# schemat2.net
KiCad netlist of a schematic drawn in EAGLE
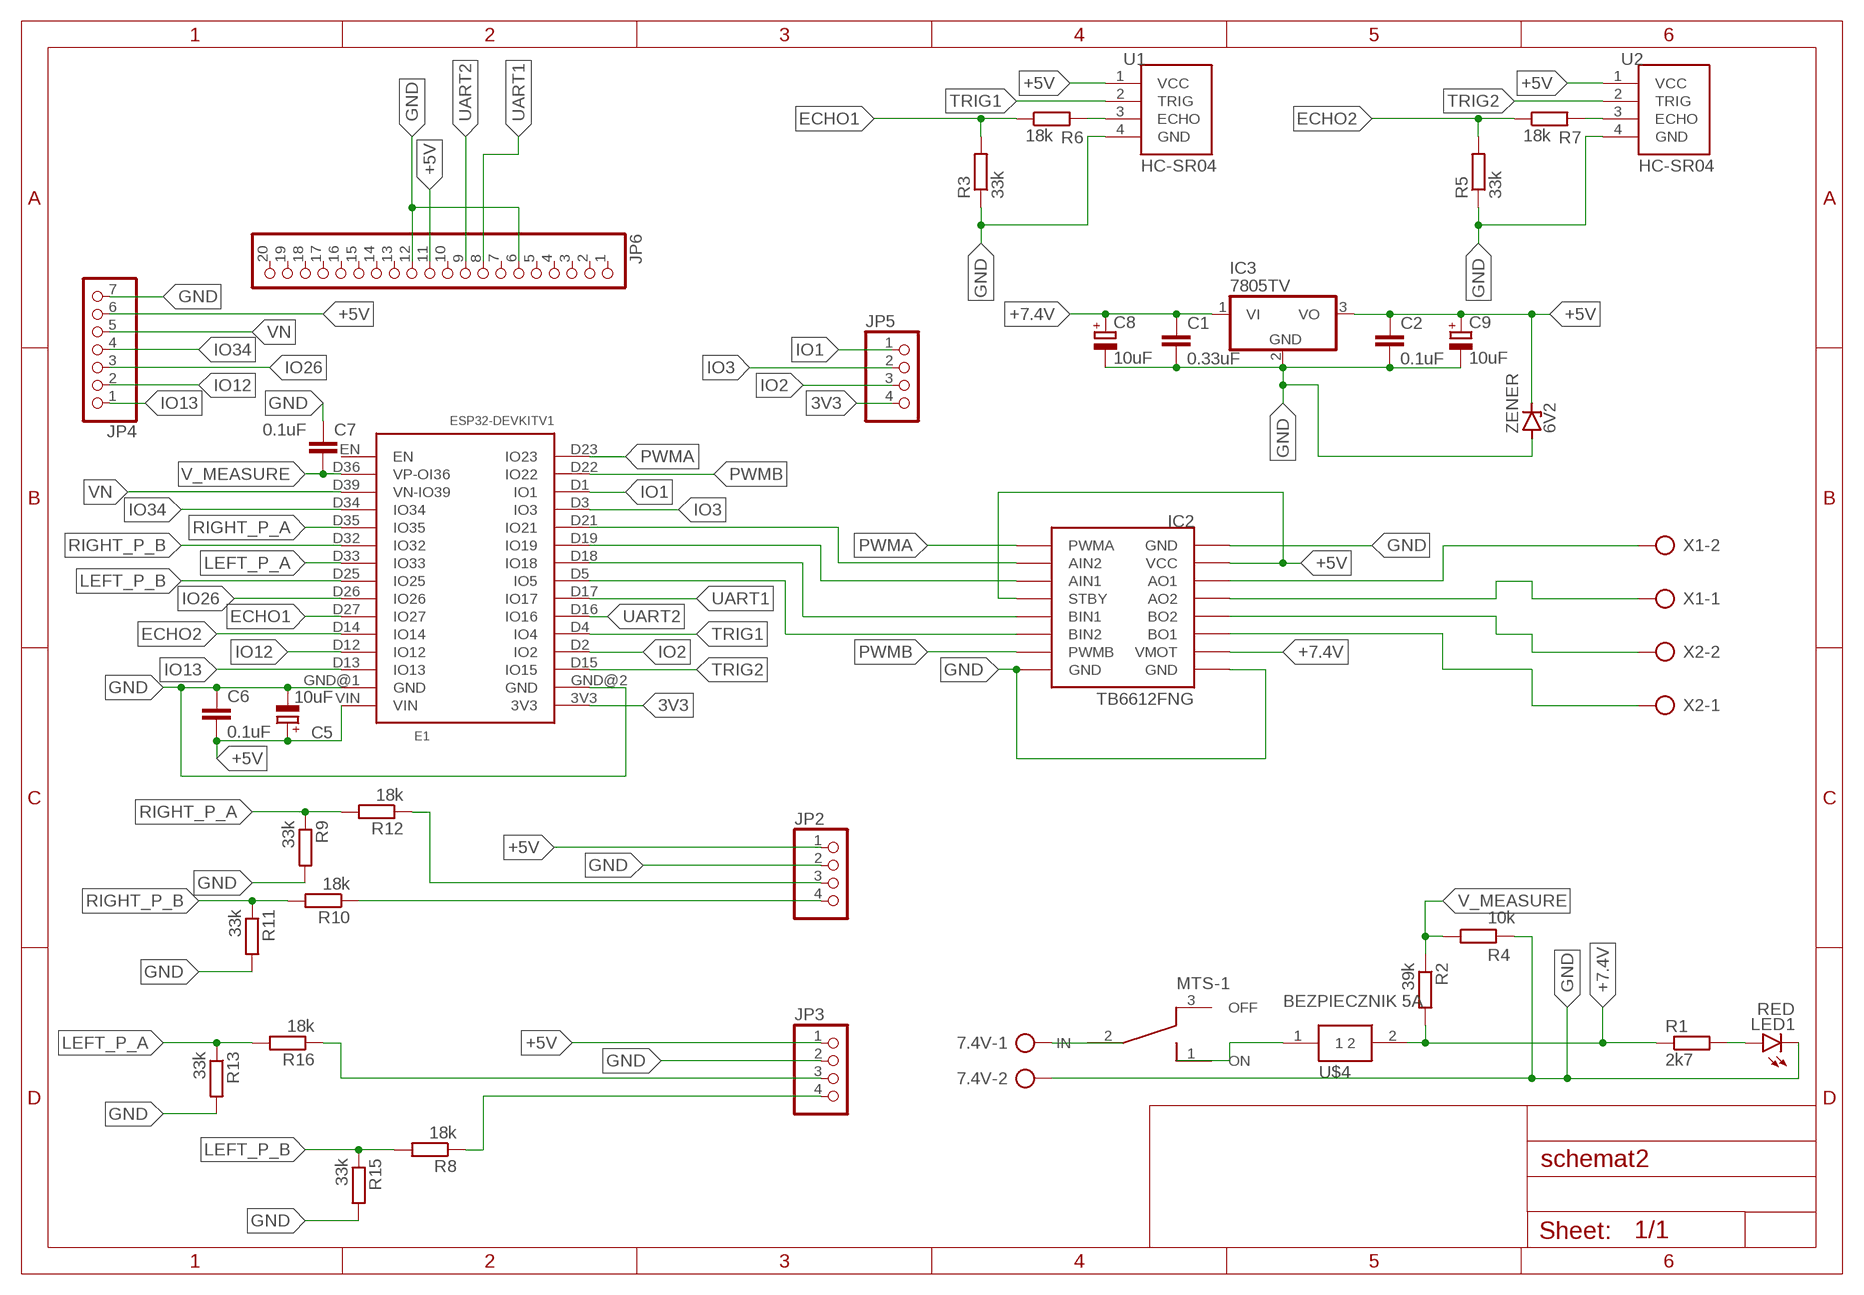
[diagram p0: schematic, sheet 1]

(export (version "E")
  (design (tool "Eeschema 10.0.6"))
  (components
    (comp (ref "7.4V")
      (value "AK500/2")
      (footprint "eagle-import:AK500_2")
      (libsource (lib "eagle-import") (part "AK500/2"))
    )
    (comp (ref "C1")
      (value "0.33uF")
      (footprint "eagle-import:C025-024X044")
      (libsource (lib "eagle-import") (part "C-EU025-024X044"))
    )
    (comp (ref "C2")
      (value "0.1uF")
      (footprint "eagle-import:C025-024X044")
      (libsource (lib "eagle-import") (part "C-EU025-024X044"))
    )
    (comp (ref "C5")
      (value "10uF")
      (footprint "eagle-import:E2,5-6E")
      (libsource (lib "eagle-import") (part "CPOL-EUE2,5-6E"))
    )
    (comp (ref "C6")
      (value "0.1uF")
      (footprint "eagle-import:C025-024X044")
      (libsource (lib "eagle-import") (part "C-EU025-024X044"))
    )
    (comp (ref "C7")
      (value "0.1uF")
      (footprint "eagle-import:C025-024X044")
      (libsource (lib "eagle-import") (part "C-EU025-024X044"))
    )
    (comp (ref "C8")
      (value "10uF")
      (footprint "eagle-import:E2,5-6E")
      (libsource (lib "eagle-import") (part "CPOL-EUE2,5-6E"))
    )
    (comp (ref "C9")
      (value "10uF")
      (footprint "eagle-import:E2,5-6E")
      (libsource (lib "eagle-import") (part "CPOL-EUE2,5-6E"))
    )
    (comp (ref "E1")
      (value "ESP32DEVKITV1")
      (footprint "eagle-import:ESP32-DEVKITV1")
      (libsource (lib "eagle-import") (part "ESP32DEVKITV1"))
    )
    (comp (ref "IC2")
      (value "MODUL_POLOLU")
      (footprint "eagle-import:MODUL_POLOLU")
      (libsource (lib "eagle-import") (part "MODUL_POLOLU"))
    )
    (comp (ref "IC3")
      (value "7805TV")
      (footprint "eagle-import:TO220V")
      (libsource (lib "eagle-import") (part "78TV05"))
    )
    (comp (ref "JP2")
      (value "PINHD-1X4")
      (footprint "eagle-import:1X04")
      (libsource (lib "eagle-import") (part "PINHD-1X4"))
    )
    (comp (ref "JP3")
      (value "PINHD-1X4")
      (footprint "eagle-import:1X04")
      (libsource (lib "eagle-import") (part "PINHD-1X4"))
    )
    (comp (ref "JP4")
      (value "PINHD-1X7")
      (footprint "eagle-import:1X07")
      (libsource (lib "eagle-import") (part "PINHD-1X7"))
    )
    (comp (ref "JP5")
      (value "PINHD-1X4")
      (footprint "eagle-import:1X04")
      (libsource (lib "eagle-import") (part "PINHD-1X4"))
    )
    (comp (ref "JP6")
      (value "PINHD-1X20")
      (footprint "eagle-import:1X20")
      (libsource (lib "eagle-import") (part "PINHD-1X20"))
    )
    (comp (ref "LED1")
      (value "RED")
      (footprint "eagle-import:LED5MM")
      (libsource (lib "eagle-import") (part "LED5MM"))
    )
    (comp (ref "R1")
      (value "2k7")
      (footprint "eagle-import:0207_5V")
      (libsource (lib "eagle-import") (part "R-EU_0207/5V"))
    )
    (comp (ref "R2")
      (value "39k")
      (footprint "eagle-import:0207_5V")
      (libsource (lib "eagle-import") (part "R-EU_0207/5V"))
    )
    (comp (ref "R3")
      (value "33k")
      (footprint "eagle-import:0207_5V")
      (libsource (lib "eagle-import") (part "R-EU_0207/5V"))
    )
    (comp (ref "R4")
      (value "10k")
      (footprint "eagle-import:0207_5V")
      (libsource (lib "eagle-import") (part "R-EU_0207/5V"))
    )
    (comp (ref "R5")
      (value "33k")
      (footprint "eagle-import:0207_5V")
      (libsource (lib "eagle-import") (part "R-EU_0207/5V"))
    )
    (comp (ref "R6")
      (value "18k")
      (footprint "eagle-import:0207_5V")
      (libsource (lib "eagle-import") (part "R-EU_0207/5V"))
    )
    (comp (ref "R7")
      (value "18k")
      (footprint "eagle-import:0207_5V")
      (libsource (lib "eagle-import") (part "R-EU_0207/5V"))
    )
    (comp (ref "R8")
      (value "18k")
      (footprint "eagle-import:0207_5V")
      (libsource (lib "eagle-import") (part "R-EU_0207/5V"))
    )
    (comp (ref "R9")
      (value "33k")
      (footprint "eagle-import:0207_5V")
      (libsource (lib "eagle-import") (part "R-EU_0207/5V"))
    )
    (comp (ref "R10")
      (value "18k")
      (footprint "eagle-import:0207_5V")
      (libsource (lib "eagle-import") (part "R-EU_0207/5V"))
    )
    (comp (ref "R11")
      (value "33k")
      (footprint "eagle-import:0207_5V")
      (libsource (lib "eagle-import") (part "R-EU_0207/5V"))
    )
    (comp (ref "R12")
      (value "18k")
      (footprint "eagle-import:0207_5V")
      (libsource (lib "eagle-import") (part "R-EU_0207/5V"))
    )
    (comp (ref "R13")
      (value "33k")
      (footprint "eagle-import:0207_5V")
      (libsource (lib "eagle-import") (part "R-EU_0207/5V"))
    )
    (comp (ref "R15")
      (value "33k")
      (footprint "eagle-import:0207_5V")
      (libsource (lib "eagle-import") (part "R-EU_0207/5V"))
    )
    (comp (ref "R16")
      (value "18k")
      (footprint "eagle-import:0207_5V")
      (libsource (lib "eagle-import") (part "R-EU_0207/5V"))
    )
    (comp (ref "U$1")
      (value "MTS-1")
      (footprint "eagle-import:SWITCH_TOGGLE")
      (libsource (lib "eagle-import") (part "MTS-1"))
    )
    (comp (ref "U$4")
      (value "BEZPIECZNIK 5A")
      (footprint "eagle-import:BEZPIECZNIK_GNIAZDO")
      (libsource (lib "eagle-import") (part "BEZPIECZNIK"))
    )
    (comp (ref "U1")
      (value "HC-SR04")
      (footprint "eagle-import:XCVR_HC-SR04")
      (fields (field (name "MF") "SparkFun Electronics"))
      (libsource (lib "eagle-import") (part "HC-SR04"))
    )
    (comp (ref "U2")
      (value "HC-SR04")
      (footprint "eagle-import:XCVR_HC-SR04")
      (fields (field (name "MF") "SparkFun Electronics"))
      (libsource (lib "eagle-import") (part "HC-SR04"))
    )
    (comp (ref "X1")
      (value "AK500/2")
      (footprint "eagle-import:AK500_2")
      (libsource (lib "eagle-import") (part "AK500/2"))
    )
    (comp (ref "X2")
      (value "AK500/2")
      (footprint "eagle-import:AK500_2")
      (libsource (lib "eagle-import") (part "AK500/2"))
    )
    (comp (ref "ZENER")
      (value "6V2")
      (footprint "eagle-import:DO35Z10")
      (libsource (lib "eagle-import") (part "1N821"))
    )
  )
  (nets
    (net (code "1") (name "+5V") (class "Default")
      (node (ref "C2") (pin "1") (pinfunction "1_1") (pintype "passive"))
      (node (ref "C5") (pin "+") (pinfunction "+_+") (pintype "passive"))
      (node (ref "C6") (pin "2") (pinfunction "2_2") (pintype "passive"))
      (node (ref "C9") (pin "+") (pinfunction "+_+") (pintype "passive"))
      (node (ref "E1") (pin "VIN") (pinfunction "VIN_VIN") (pintype "bidirectional"))
      (node (ref "IC2") (pin "STBY") (pinfunction "STBY_STBY") (pintype "bidirectional"))
      (node (ref "IC2") (pin "VCC") (pinfunction "VCC_VCC") (pintype "bidirectional"))
      (node (ref "IC3") (pin "3") (pinfunction "VO_3") (pintype "passive"))
      (node (ref "JP2") (pin "1") (pinfunction "1_1") (pintype "passive"))
      (node (ref "JP3") (pin "1") (pinfunction "1_1") (pintype "passive"))
      (node (ref "JP4") (pin "6") (pinfunction "6_6") (pintype "passive"))
      (node (ref "JP6") (pin "11") (pinfunction "11_11") (pintype "passive"))
      (node (ref "U1") (pin "1") (pinfunction "VCC_1") (pintype "power_in"))
      (node (ref "U2") (pin "1") (pinfunction "VCC_1") (pintype "power_in"))
      (node (ref "ZENER") (pin "C") (pinfunction "C_C") (pintype "passive"))
    )
    (net (code "2") (name "+7.4V") (class "Default")
      (node (ref "C1") (pin "1") (pinfunction "1_1") (pintype "passive"))
      (node (ref "C8") (pin "+") (pinfunction "+_+") (pintype "passive"))
      (node (ref "IC2") (pin "VMOT") (pinfunction "VMOT_VMOT") (pintype "bidirectional"))
      (node (ref "IC3") (pin "1") (pinfunction "VI_1") (pintype "input"))
      (node (ref "R1") (pin "1") (pinfunction "1_1") (pintype "passive"))
      (node (ref "R2") (pin "2") (pinfunction "2_2") (pintype "passive"))
      (node (ref "U$4") (pin "2") (pinfunction "2_2") (pintype "bidirectional"))
    )
    (net (code "3") (name "3V3") (class "Default")
      (node (ref "E1") (pin "3V3") (pinfunction "3V3_3V3") (pintype "bidirectional"))
      (node (ref "JP5") (pin "4") (pinfunction "4_4") (pintype "passive"))
    )
    (net (code "4") (name "ECHO1") (class "Default")
      (node (ref "E1") (pin "D27") (pinfunction "IO27_D27") (pintype "bidirectional"))
      (node (ref "R3") (pin "2") (pinfunction "2_2") (pintype "passive"))
      (node (ref "R6") (pin "1") (pinfunction "1_1") (pintype "passive"))
    )
    (net (code "5") (name "ECHO2") (class "Default")
      (node (ref "E1") (pin "D14") (pinfunction "IO14_D14") (pintype "bidirectional"))
      (node (ref "R5") (pin "2") (pinfunction "2_2") (pintype "passive"))
      (node (ref "R7") (pin "1") (pinfunction "1_1") (pintype "passive"))
    )
    (net (code "6") (name "GND") (class "Default")
      (node (ref "7.4V") (pin "2") (pinfunction "KL_2") (pintype "passive"))
      (node (ref "C1") (pin "2") (pinfunction "2_2") (pintype "passive"))
      (node (ref "C2") (pin "2") (pinfunction "2_2") (pintype "passive"))
      (node (ref "C5") (pin "-") (pinfunction "-_-") (pintype "passive"))
      (node (ref "C6") (pin "1") (pinfunction "1_1") (pintype "passive"))
      (node (ref "C7") (pin "1") (pinfunction "1_1") (pintype "passive"))
      (node (ref "C8") (pin "-") (pinfunction "-_-") (pintype "passive"))
      (node (ref "C9") (pin "-") (pinfunction "-_-") (pintype "passive"))
      (node (ref "E1") (pin "GND@1") (pinfunction "GND_GND@1") (pintype "bidirectional"))
      (node (ref "E1") (pin "GND@2") (pinfunction "GND_GND@2") (pintype "bidirectional"))
      (node (ref "IC2") (pin "GND1") (pinfunction "GND_GND1") (pintype "bidirectional"))
      (node (ref "IC2") (pin "GND2") (pinfunction "GND_GND2") (pintype "bidirectional"))
      (node (ref "IC2") (pin "GND3") (pinfunction "GND_GND3") (pintype "bidirectional"))
      (node (ref "IC3") (pin "2") (pinfunction "GND_2") (pintype "passive"))
      (node (ref "JP2") (pin "2") (pinfunction "2_2") (pintype "passive"))
      (node (ref "JP3") (pin "2") (pinfunction "2_2") (pintype "passive"))
      (node (ref "JP4") (pin "7") (pinfunction "7_7") (pintype "passive"))
      (node (ref "JP6") (pin "12") (pinfunction "12_12") (pintype "passive"))
      (node (ref "JP6") (pin "6") (pinfunction "6_6") (pintype "passive"))
      (node (ref "LED1") (pin "K") (pinfunction "C_K") (pintype "passive"))
      (node (ref "R11") (pin "2") (pinfunction "2_2") (pintype "passive"))
      (node (ref "R13") (pin "2") (pinfunction "2_2") (pintype "passive"))
      (node (ref "R15") (pin "2") (pinfunction "2_2") (pintype "passive"))
      (node (ref "R3") (pin "1") (pinfunction "1_1") (pintype "passive"))
      (node (ref "R4") (pin "2") (pinfunction "2_2") (pintype "passive"))
      (node (ref "R5") (pin "1") (pinfunction "1_1") (pintype "passive"))
      (node (ref "R9") (pin "2") (pinfunction "2_2") (pintype "passive"))
      (node (ref "U1") (pin "4") (pinfunction "GND_4") (pintype "power_in"))
      (node (ref "U2") (pin "4") (pinfunction "GND_4") (pintype "power_in"))
      (node (ref "ZENER") (pin "A") (pinfunction "A_A") (pintype "passive"))
    )
    (net (code "7") (name "IO1") (class "Default")
      (node (ref "E1") (pin "D1") (pinfunction "IO1_D1") (pintype "bidirectional"))
      (node (ref "JP5") (pin "1") (pinfunction "1_1") (pintype "passive"))
    )
    (net (code "8") (name "IO2") (class "Default")
      (node (ref "E1") (pin "D2") (pinfunction "IO2_D2") (pintype "bidirectional"))
      (node (ref "JP5") (pin "3") (pinfunction "3_3") (pintype "passive"))
    )
    (net (code "9") (name "IO3") (class "Default")
      (node (ref "E1") (pin "D3") (pinfunction "IO3_D3") (pintype "bidirectional"))
      (node (ref "JP5") (pin "2") (pinfunction "2_2") (pintype "passive"))
    )
    (net (code "10") (name "IO12") (class "Default")
      (node (ref "E1") (pin "D12") (pinfunction "IO12_D12") (pintype "bidirectional"))
      (node (ref "JP4") (pin "2") (pinfunction "2_2") (pintype "passive"))
    )
    (net (code "11") (name "IO13") (class "Default")
      (node (ref "E1") (pin "D13") (pinfunction "IO13_D13") (pintype "bidirectional"))
      (node (ref "JP4") (pin "1") (pinfunction "1_1") (pintype "passive"))
    )
    (net (code "12") (name "IO26") (class "Default")
      (node (ref "E1") (pin "D26") (pinfunction "IO26_D26") (pintype "bidirectional"))
      (node (ref "JP4") (pin "3") (pinfunction "3_3") (pintype "passive"))
    )
    (net (code "13") (name "IO34") (class "Default")
      (node (ref "E1") (pin "D34") (pinfunction "IO34_D34") (pintype "bidirectional"))
      (node (ref "JP4") (pin "4") (pinfunction "4_4") (pintype "passive"))
    )
    (net (code "14") (name "LEFT_P_A") (class "Default")
      (node (ref "E1") (pin "D33") (pinfunction "IO33_D33") (pintype "bidirectional"))
      (node (ref "R13") (pin "1") (pinfunction "1_1") (pintype "passive"))
      (node (ref "R16") (pin "2") (pinfunction "2_2") (pintype "passive"))
    )
    (net (code "15") (name "LEFT_P_B") (class "Default")
      (node (ref "E1") (pin "D25") (pinfunction "IO25_D25") (pintype "bidirectional"))
      (node (ref "R15") (pin "1") (pinfunction "1_1") (pintype "passive"))
      (node (ref "R8") (pin "2") (pinfunction "2_2") (pintype "passive"))
    )
    (net (code "16") (name "Net-(7.4VA-KL)") (class "Default")
      (node (ref "7.4V") (pin "1") (pinfunction "KL_1") (pintype "passive"))
      (node (ref "U$1") (pin "2") (pinfunction "IN_2") (pintype "bidirectional"))
    )
    (net (code "17") (name "Net-(E1-IO5)") (class "Default")
      (node (ref "E1") (pin "D5") (pinfunction "IO5_D5") (pintype "bidirectional"))
      (node (ref "IC2") (pin "BIN2") (pinfunction "BIN2_BIN2") (pintype "bidirectional"))
    )
    (net (code "18") (name "Net-(E1-IO18)") (class "Default")
      (node (ref "E1") (pin "D18") (pinfunction "IO18_D18") (pintype "bidirectional"))
      (node (ref "IC2") (pin "BIN1") (pinfunction "BIN1_BIN1") (pintype "bidirectional"))
    )
    (net (code "19") (name "Net-(E1-IO19)") (class "Default")
      (node (ref "E1") (pin "D19") (pinfunction "IO19_D19") (pintype "bidirectional"))
      (node (ref "IC2") (pin "AIN1") (pinfunction "AIN1_AIN1") (pintype "bidirectional"))
    )
    (net (code "20") (name "Net-(E1-IO21)") (class "Default")
      (node (ref "E1") (pin "D21") (pinfunction "IO21_D21") (pintype "bidirectional"))
      (node (ref "IC2") (pin "AIN2") (pinfunction "AIN2_AIN2") (pintype "bidirectional"))
    )
    (net (code "21") (name "Net-(IC2-AO2)") (class "Default")
      (node (ref "IC2") (pin "A02") (pinfunction "AO2_A02") (pintype "bidirectional"))
      (node (ref "X1") (pin "1") (pinfunction "KL_1") (pintype "passive"))
    )
    (net (code "22") (name "Net-(JP2-Pad3)") (class "Default")
      (node (ref "JP2") (pin "3") (pinfunction "3_3") (pintype "passive"))
      (node (ref "R12") (pin "1") (pinfunction "1_1") (pintype "passive"))
    )
    (net (code "23") (name "Net-(JP2-Pad4)") (class "Default")
      (node (ref "JP2") (pin "4") (pinfunction "4_4") (pintype "passive"))
      (node (ref "R10") (pin "1") (pinfunction "1_1") (pintype "passive"))
    )
    (net (code "24") (name "Net-(JP3-Pad3)") (class "Default")
      (node (ref "JP3") (pin "3") (pinfunction "3_3") (pintype "passive"))
      (node (ref "R16") (pin "1") (pinfunction "1_1") (pintype "passive"))
    )
    (net (code "25") (name "Net-(JP3-Pad4)") (class "Default")
      (node (ref "JP3") (pin "4") (pinfunction "4_4") (pintype "passive"))
      (node (ref "R8") (pin "1") (pinfunction "1_1") (pintype "passive"))
    )
    (net (code "26") (name "Net-(LED1-PadA)") (class "Default")
      (node (ref "LED1") (pin "A") (pinfunction "A_A") (pintype "passive"))
      (node (ref "R1") (pin "2") (pinfunction "2_2") (pintype "passive"))
    )
    (net (code "27") (name "Net-(U$1-ON)") (class "Default")
      (node (ref "U$1") (pin "1") (pinfunction "ON_1") (pintype "bidirectional"))
      (node (ref "U$4") (pin "1") (pinfunction "1_1") (pintype "bidirectional"))
    )
    (net (code "28") (name "Net-(U1-ECHO)") (class "Default")
      (node (ref "R6") (pin "2") (pinfunction "2_2") (pintype "passive"))
      (node (ref "U1") (pin "3") (pinfunction "ECHO_3") (pintype "bidirectional"))
    )
    (net (code "29") (name "Net-(U2-ECHO)") (class "Default")
      (node (ref "R7") (pin "2") (pinfunction "2_2") (pintype "passive"))
      (node (ref "U2") (pin "3") (pinfunction "ECHO_3") (pintype "bidirectional"))
    )
    (net (code "30") (name "Net-(X1B-KL)") (class "Default")
      (node (ref "IC2") (pin "AO1") (pinfunction "AO1_AO1") (pintype "bidirectional"))
      (node (ref "X1") (pin "2") (pinfunction "KL_2") (pintype "passive"))
    )
    (net (code "31") (name "Net-(X2A-KL)") (class "Default")
      (node (ref "IC2") (pin "BO1") (pinfunction "BO1_BO1") (pintype "bidirectional"))
      (node (ref "X2") (pin "1") (pinfunction "KL_1") (pintype "passive"))
    )
    (net (code "32") (name "Net-(X2B-KL)") (class "Default")
      (node (ref "IC2") (pin "BO2") (pinfunction "BO2_BO2") (pintype "bidirectional"))
      (node (ref "X2") (pin "2") (pinfunction "KL_2") (pintype "passive"))
    )
    (net (code "33") (name "PWMA") (class "Default")
      (node (ref "E1") (pin "D23") (pinfunction "IO23_D23") (pintype "bidirectional"))
      (node (ref "IC2") (pin "PWMA") (pinfunction "PWMA_PWMA") (pintype "bidirectional"))
    )
    (net (code "34") (name "PWMB") (class "Default")
      (node (ref "E1") (pin "D22") (pinfunction "IO22_D22") (pintype "bidirectional"))
      (node (ref "IC2") (pin "PWMB") (pinfunction "PWMB_PWMB") (pintype "bidirectional"))
    )
    (net (code "35") (name "RIGHT_P_A") (class "Default")
      (node (ref "E1") (pin "D35") (pinfunction "IO35_D35") (pintype "bidirectional"))
      (node (ref "R12") (pin "2") (pinfunction "2_2") (pintype "passive"))
      (node (ref "R9") (pin "1") (pinfunction "1_1") (pintype "passive"))
    )
    (net (code "36") (name "RIGHT_P_B") (class "Default")
      (node (ref "E1") (pin "D32") (pinfunction "IO32_D32") (pintype "bidirectional"))
      (node (ref "R10") (pin "2") (pinfunction "2_2") (pintype "passive"))
      (node (ref "R11") (pin "1") (pinfunction "1_1") (pintype "passive"))
    )
    (net (code "37") (name "TRIG1") (class "Default")
      (node (ref "E1") (pin "D4") (pinfunction "IO4_D4") (pintype "bidirectional"))
      (node (ref "U1") (pin "2") (pinfunction "TRIG_2") (pintype "bidirectional"))
    )
    (net (code "38") (name "TRIG2") (class "Default")
      (node (ref "E1") (pin "D15") (pinfunction "IO15_D15") (pintype "bidirectional"))
      (node (ref "U2") (pin "2") (pinfunction "TRIG_2") (pintype "bidirectional"))
    )
    (net (code "39") (name "UART1") (class "Default")
      (node (ref "E1") (pin "D17") (pinfunction "IO17_D17") (pintype "bidirectional"))
      (node (ref "JP6") (pin "8") (pinfunction "8_8") (pintype "passive"))
    )
    (net (code "40") (name "UART2") (class "Default")
      (node (ref "E1") (pin "D16") (pinfunction "IO16_D16") (pintype "bidirectional"))
      (node (ref "JP6") (pin "9") (pinfunction "9_9") (pintype "passive"))
    )
    (net (code "41") (name "VN") (class "Default")
      (node (ref "E1") (pin "D39") (pinfunction "VN-IO39_D39") (pintype "bidirectional"))
      (node (ref "JP4") (pin "5") (pinfunction "5_5") (pintype "passive"))
    )
    (net (code "42") (name "V_MEASURE") (class "Default")
      (node (ref "C7") (pin "2") (pinfunction "2_2") (pintype "passive"))
      (node (ref "E1") (pin "D36") (pinfunction "VP-OI36_D36") (pintype "bidirectional"))
      (node (ref "R2") (pin "1") (pinfunction "1_1") (pintype "passive"))
      (node (ref "R4") (pin "1") (pinfunction "1_1") (pintype "passive"))
    )
    (net (code "43") (name "unconnected-(E1-PadEN)") (class "Default")
      (node (ref "E1") (pin "EN") (pinfunction "EN_EN") (pintype "bidirectional"))
    )
    (net (code "44") (name "unconnected-(JP6-Pad1)") (class "Default")
      (node (ref "JP6") (pin "1") (pinfunction "1_1") (pintype "passive"))
    )
    (net (code "45") (name "unconnected-(JP6-Pad2)") (class "Default")
      (node (ref "JP6") (pin "2") (pinfunction "2_2") (pintype "passive"))
    )
    (net (code "46") (name "unconnected-(JP6-Pad3)") (class "Default")
      (node (ref "JP6") (pin "3") (pinfunction "3_3") (pintype "passive"))
    )
    (net (code "47") (name "unconnected-(JP6-Pad4)") (class "Default")
      (node (ref "JP6") (pin "4") (pinfunction "4_4") (pintype "passive"))
    )
    (net (code "48") (name "unconnected-(JP6-Pad5)") (class "Default")
      (node (ref "JP6") (pin "5") (pinfunction "5_5") (pintype "passive"))
    )
    (net (code "49") (name "unconnected-(JP6-Pad7)") (class "Default")
      (node (ref "JP6") (pin "7") (pinfunction "7_7") (pintype "passive"))
    )
    (net (code "50") (name "unconnected-(JP6-Pad10)") (class "Default")
      (node (ref "JP6") (pin "10") (pinfunction "10_10") (pintype "passive"))
    )
    (net (code "51") (name "unconnected-(JP6-Pad13)") (class "Default")
      (node (ref "JP6") (pin "13") (pinfunction "13_13") (pintype "passive"))
    )
    (net (code "52") (name "unconnected-(JP6-Pad14)") (class "Default")
      (node (ref "JP6") (pin "14") (pinfunction "14_14") (pintype "passive"))
    )
    (net (code "53") (name "unconnected-(JP6-Pad15)") (class "Default")
      (node (ref "JP6") (pin "15") (pinfunction "15_15") (pintype "passive"))
    )
    (net (code "54") (name "unconnected-(JP6-Pad16)") (class "Default")
      (node (ref "JP6") (pin "16") (pinfunction "16_16") (pintype "passive"))
    )
    (net (code "55") (name "unconnected-(JP6-Pad17)") (class "Default")
      (node (ref "JP6") (pin "17") (pinfunction "17_17") (pintype "passive"))
    )
    (net (code "56") (name "unconnected-(JP6-Pad18)") (class "Default")
      (node (ref "JP6") (pin "18") (pinfunction "18_18") (pintype "passive"))
    )
    (net (code "57") (name "unconnected-(JP6-Pad19)") (class "Default")
      (node (ref "JP6") (pin "19") (pinfunction "19_19") (pintype "passive"))
    )
    (net (code "58") (name "unconnected-(JP6-Pad20)") (class "Default")
      (node (ref "JP6") (pin "20") (pinfunction "20_20") (pintype "passive"))
    )
    (net (code "59") (name "unconnected-(U$1-OFF-Pad3)") (class "Default")
      (node (ref "U$1") (pin "3") (pinfunction "OFF_3") (pintype "bidirectional"))
    )
  )
)
